# Cortex.net
KiCad netlist of a schematic drawn in Altium Designer
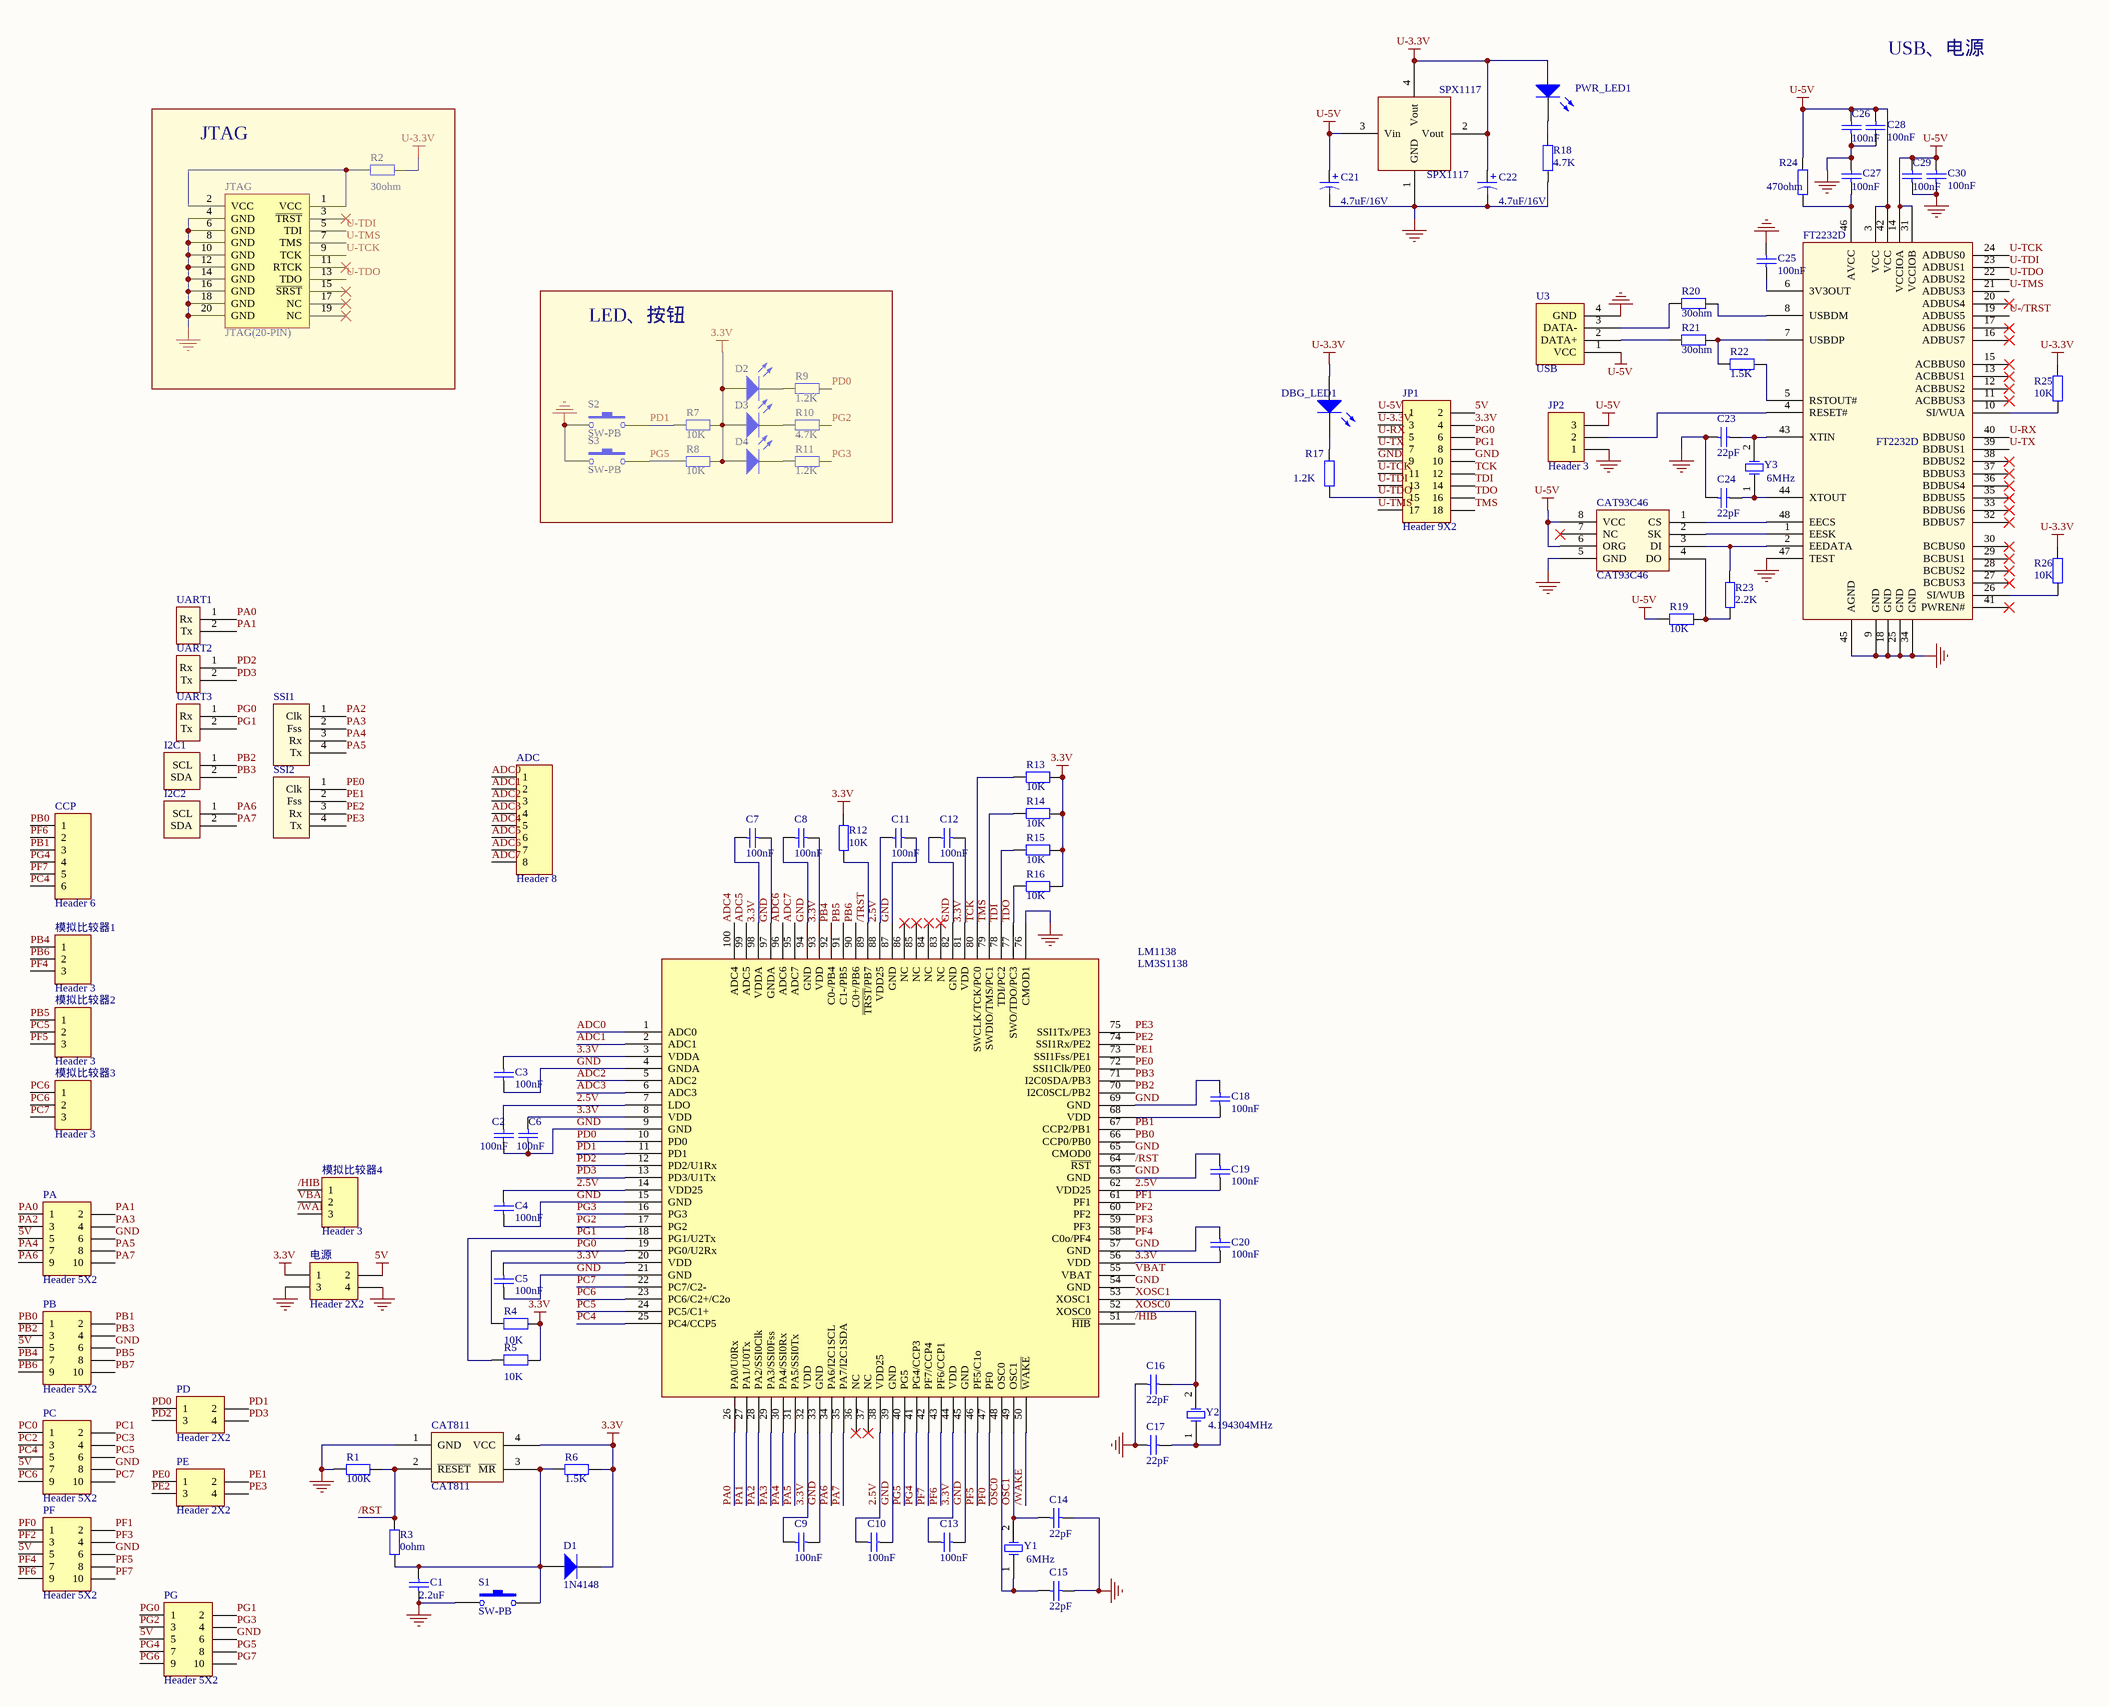
[diagram p0: Cortex.SchDoc]

(export (version "E")
  (design (tool "Eeschema 10.0.6"))
  (components
    (comp (ref "ADC")
      (value "Header 8")
      (footprint "HDR1X8")
      (description "Header, 8-Pin")
      (fields (field (name "PUBLISHER") "Altium Limited"))
      (libsource (lib "自定义库") (part "Header 8"))
    )
    (comp (ref "C1")
      (value "2.2uF")
      (footprint "C0805")
      (description "Capacitor")
      (fields (field (name "Comment") "Cap") (field (name "PUBLISHER") "Altium Limited"))
      (libsource (lib "Miscellaneous Devices") (part "Cap"))
    )
    (comp (ref "C2")
      (value "100nF")
      (footprint "C0805")
      (description "Capacitor")
      (fields (field (name "Comment") "Cap") (field (name "PUBLISHER") "Altium Limited"))
      (libsource (lib "Miscellaneous Devices") (part "Cap"))
    )
    (comp (ref "C3")
      (value "100nF")
      (footprint "C0805")
      (description "Capacitor")
      (fields (field (name "Comment") "Cap") (field (name "PUBLISHER") "Altium Limited"))
      (libsource (lib "Miscellaneous Devices") (part "Cap"))
    )
    (comp (ref "C4")
      (value "100nF")
      (footprint "C0805")
      (description "Capacitor")
      (fields (field (name "Comment") "Cap") (field (name "PUBLISHER") "Altium Limited"))
      (libsource (lib "Miscellaneous Devices") (part "Cap"))
    )
    (comp (ref "C5")
      (value "100nF")
      (footprint "C0805")
      (description "Capacitor")
      (fields (field (name "Comment") "Cap") (field (name "PUBLISHER") "Altium Limited"))
      (libsource (lib "Miscellaneous Devices") (part "Cap"))
    )
    (comp (ref "C6")
      (value "100nF")
      (footprint "C0805")
      (description "Capacitor")
      (fields (field (name "Comment") "Cap") (field (name "PUBLISHER") "Altium Limited"))
      (libsource (lib "Miscellaneous Devices") (part "Cap"))
    )
    (comp (ref "C7")
      (value "100nF")
      (footprint "C0805")
      (description "Capacitor")
      (fields (field (name "Comment") "Cap") (field (name "PUBLISHER") "Altium Limited"))
      (libsource (lib "Miscellaneous Devices") (part "Cap"))
    )
    (comp (ref "C8")
      (value "100nF")
      (footprint "C0805")
      (description "Capacitor")
      (fields (field (name "Comment") "Cap") (field (name "PUBLISHER") "Altium Limited"))
      (libsource (lib "Miscellaneous Devices") (part "Cap"))
    )
    (comp (ref "C9")
      (value "100nF")
      (footprint "C0805")
      (description "Capacitor")
      (fields (field (name "Comment") "Cap") (field (name "PUBLISHER") "Altium Limited"))
      (libsource (lib "Miscellaneous Devices") (part "Cap"))
    )
    (comp (ref "C10")
      (value "100nF")
      (footprint "C0805")
      (description "Capacitor")
      (fields (field (name "Comment") "Cap") (field (name "PUBLISHER") "Altium Limited"))
      (libsource (lib "Miscellaneous Devices") (part "Cap"))
    )
    (comp (ref "C11")
      (value "100nF")
      (footprint "C0805")
      (description "Capacitor")
      (fields (field (name "Comment") "Cap") (field (name "PUBLISHER") "Altium Limited"))
      (libsource (lib "Miscellaneous Devices") (part "Cap"))
    )
    (comp (ref "C12")
      (value "100nF")
      (footprint "C0805")
      (description "Capacitor")
      (fields (field (name "Comment") "Cap") (field (name "PUBLISHER") "Altium Limited"))
      (libsource (lib "Miscellaneous Devices") (part "Cap"))
    )
    (comp (ref "C13")
      (value "100nF")
      (footprint "C0805")
      (description "Capacitor")
      (fields (field (name "Comment") "Cap") (field (name "PUBLISHER") "Altium Limited"))
      (libsource (lib "Miscellaneous Devices") (part "Cap"))
    )
    (comp (ref "C14")
      (value "22pF")
      (footprint "C0805")
      (description "Capacitor")
      (fields (field (name "Comment") "Cap") (field (name "PUBLISHER") "Altium Limited"))
      (libsource (lib "Miscellaneous Devices") (part "Cap"))
    )
    (comp (ref "C15")
      (value "22pF")
      (footprint "C0805")
      (description "Capacitor")
      (fields (field (name "Comment") "Cap") (field (name "PUBLISHER") "Altium Limited"))
      (libsource (lib "Miscellaneous Devices") (part "Cap"))
    )
    (comp (ref "C16")
      (value "22pF")
      (footprint "C0805")
      (description "Capacitor")
      (fields (field (name "Comment") "Cap") (field (name "PUBLISHER") "Altium Limited"))
      (libsource (lib "Miscellaneous Devices") (part "Cap"))
    )
    (comp (ref "C17")
      (value "22pF")
      (footprint "C0805")
      (description "Capacitor")
      (fields (field (name "Comment") "Cap") (field (name "PUBLISHER") "Altium Limited"))
      (libsource (lib "Miscellaneous Devices") (part "Cap"))
    )
    (comp (ref "C18")
      (value "100nF")
      (footprint "C0805")
      (description "Capacitor")
      (fields (field (name "Comment") "Cap") (field (name "PUBLISHER") "Altium Limited"))
      (libsource (lib "Miscellaneous Devices") (part "Cap"))
    )
    (comp (ref "C19")
      (value "100nF")
      (footprint "C0805")
      (description "Capacitor")
      (fields (field (name "Comment") "Cap") (field (name "PUBLISHER") "Altium Limited"))
      (libsource (lib "Miscellaneous Devices") (part "Cap"))
    )
    (comp (ref "C20")
      (value "100nF")
      (footprint "C0805")
      (description "Capacitor")
      (fields (field (name "Comment") "Cap") (field (name "PUBLISHER") "Altium Limited"))
      (libsource (lib "Miscellaneous Devices") (part "Cap"))
    )
    (comp (ref "C21")
      (value "4.7uF/16V")
      (footprint "C1206")
      (description "Polarized Capacitor (Radial)")
      (fields (field (name "Comment") "Cap Pol1") (field (name "PUBLISHER") "Altium Limited"))
      (libsource (lib "Miscellaneous Devices") (part "Cap Pol1"))
    )
    (comp (ref "C22")
      (value "4.7uF/16V")
      (footprint "C1206")
      (description "Polarized Capacitor (Radial)")
      (fields (field (name "Comment") "Cap Pol1") (field (name "PUBLISHER") "Altium Limited"))
      (libsource (lib "Miscellaneous Devices") (part "Cap Pol1"))
    )
    (comp (ref "C23")
      (value "22pF")
      (footprint "C0805")
      (description "Capacitor")
      (fields (field (name "Comment") "Cap") (field (name "PUBLISHER") "Altium Limited"))
      (libsource (lib "Miscellaneous Devices") (part "Cap"))
    )
    (comp (ref "C24")
      (value "22pF")
      (footprint "C0805")
      (description "Capacitor")
      (fields (field (name "Comment") "Cap") (field (name "PUBLISHER") "Altium Limited"))
      (libsource (lib "Miscellaneous Devices") (part "Cap"))
    )
    (comp (ref "C25")
      (value "100nF")
      (footprint "C0805")
      (description "Capacitor")
      (fields (field (name "Comment") "Cap") (field (name "PUBLISHER") "Altium Limited"))
      (libsource (lib "Miscellaneous Devices") (part "Cap"))
    )
    (comp (ref "C26")
      (value "100nF")
      (footprint "C0805")
      (description "Capacitor")
      (fields (field (name "Comment") "Cap") (field (name "PUBLISHER") "Altium Limited"))
      (libsource (lib "Miscellaneous Devices") (part "Cap"))
    )
    (comp (ref "C27")
      (value "100nF")
      (footprint "C0805")
      (description "Capacitor")
      (fields (field (name "Comment") "Cap") (field (name "PUBLISHER") "Altium Limited"))
      (libsource (lib "Miscellaneous Devices") (part "Cap"))
    )
    (comp (ref "C28")
      (value "100nF")
      (footprint "C0805")
      (description "Capacitor")
      (fields (field (name "Comment") "Cap") (field (name "PUBLISHER") "Altium Limited"))
      (libsource (lib "Miscellaneous Devices") (part "Cap"))
    )
    (comp (ref "C29")
      (value "100nF")
      (footprint "C0805")
      (description "Capacitor")
      (fields (field (name "Comment") "Cap") (field (name "PUBLISHER") "Altium Limited"))
      (libsource (lib "Miscellaneous Devices") (part "Cap"))
    )
    (comp (ref "C30")
      (value "100nF")
      (footprint "C0805")
      (description "Capacitor")
      (fields (field (name "Comment") "Cap") (field (name "PUBLISHER") "Altium Limited"))
      (libsource (lib "Miscellaneous Devices") (part "Cap"))
    )
    (comp (ref "CAT93C46") (value "CAT93C46") (footprint "SO8") (libsource (lib "自定义库") (part "CAT93C46")))
    (comp (ref "CAT811") (value "CAT811") (footprint "SOT-143") (libsource (lib "自定义库") (part "CAT811")))
    (comp (ref "CCP")
      (value "Header 6")
      (footprint "HDR1X6")
      (description "Header, 6-Pin")
      (fields (field (name "PUBLISHER") "Altium Limited"))
      (libsource (lib "自定义库") (part "Header 6"))
    )
    (comp (ref "D1")
      (value "1N4148")
      (footprint "DO-35")
      (description "High Conductance Fast Diode")
      (fields (field (name "PUBLISHER") "Altium Limited"))
      (libsource (lib "自定义库") (part "Diode 1N4148"))
    )
    (comp (ref "D2")
      (value "LED2")
      (footprint "3.2X1.6X1.1")
      (description "Typical RED, GREEN, YELLOW, AMBER GaAs LED")
      (fields (field (name "PUBLISHER") "Altium Limited"))
      (libsource (lib "自定义库") (part "LED2"))
    )
    (comp (ref "D3")
      (value "LED2")
      (footprint "3.2X1.6X1.1")
      (description "Typical RED, GREEN, YELLOW, AMBER GaAs LED")
      (fields (field (name "PUBLISHER") "Altium Limited"))
      (libsource (lib "自定义库") (part "LED2"))
    )
    (comp (ref "D4")
      (value "LED2")
      (footprint "3.2X1.6X1.1")
      (description "Typical RED, GREEN, YELLOW, AMBER GaAs LED")
      (fields (field (name "PUBLISHER") "Altium Limited"))
      (libsource (lib "自定义库") (part "LED2"))
    )
    (comp (ref "DBG_LED1")
      (value "LED0")
      (footprint "LED-0")
      (description "Typical INFRARED GaAs LED")
      (fields (field (name "PUBLISHER") "Altium Limited"))
      (libsource (lib "自定义库") (part "LED0"))
    )
    (comp (ref "FT2232D") (value "FT2232D") (footprint "LQFP-48") (libsource (lib "自定义库") (part "FT2232D")))
    (comp (ref "I2C1") (value "I2C") (footprint "HDR1X2") (libsource (lib "自定义库") (part "I2C")))
    (comp (ref "I2C2") (value "I2C") (footprint "HDR1X2") (libsource (lib "自定义库") (part "I2C")))
    (comp (ref "JP1")
      (value "Header 9X2")
      (footprint "HDR2X9")
      (description "Header, 9-Pin, Dual row")
      (fields (field (name "PUBLISHER") "Altium Limited"))
      (libsource (lib "自定义库") (part "Header 9X2"))
    )
    (comp (ref "JP2")
      (value "Header 3")
      (footprint "HDR1X3")
      (description "Header, 3-Pin")
      (fields (field (name "PUBLISHER") "Altium Limited"))
      (libsource (lib "") (part "Header 3_1"))
    )
    (comp (ref "JTAG")
      (value "JTAG(20-PIN)")
      (footprint "IDC-20(2.54)IDE")
      (libsource (lib "自定义库") (part "JTAG(20-PIN)"))
    )
    (comp (ref "LM1138") (value "LM3S1138") (footprint "LQFP-100") (libsource (lib "自定义库") (part "LM3S1138")))
    (comp (ref "PA")
      (value "Header 5X2")
      (footprint "HDR2X5")
      (description "Header, 5-Pin, Dual row")
      (fields (field (name "PUBLISHER") "Altium Limited"))
      (libsource (lib "自定义库") (part "Header 5X2"))
    )
    (comp (ref "PB")
      (value "Header 5X2")
      (footprint "HDR2X5")
      (description "Header, 5-Pin, Dual row")
      (fields (field (name "PUBLISHER") "Altium Limited"))
      (libsource (lib "自定义库") (part "Header 5X2"))
    )
    (comp (ref "PC")
      (value "Header 5X2")
      (footprint "HDR2X5")
      (description "Header, 5-Pin, Dual row")
      (fields (field (name "PUBLISHER") "Altium Limited"))
      (libsource (lib "自定义库") (part "Header 5X2"))
    )
    (comp (ref "PD")
      (value "Header 2X2")
      (footprint "HDR2X2")
      (description "Header, 2-Pin, Dual row")
      (fields (field (name "PUBLISHER") "Altium Limited"))
      (libsource (lib "自定义库") (part "Header 2X2"))
    )
    (comp (ref "PE")
      (value "Header 2X2")
      (footprint "HDR2X2")
      (description "Header, 2-Pin, Dual row")
      (fields (field (name "PUBLISHER") "Altium Limited"))
      (libsource (lib "自定义库") (part "Header 2X2"))
    )
    (comp (ref "PF")
      (value "Header 5X2")
      (footprint "HDR2X5")
      (description "Header, 5-Pin, Dual row")
      (fields (field (name "PUBLISHER") "Altium Limited"))
      (libsource (lib "自定义库") (part "Header 5X2"))
    )
    (comp (ref "PG")
      (value "Header 5X2")
      (footprint "HDR2X5")
      (description "Header, 5-Pin, Dual row")
      (fields (field (name "PUBLISHER") "Altium Limited"))
      (libsource (lib "自定义库") (part "Header 5X2"))
    )
    (comp (ref "PWR_LED1")
      (value "LED0")
      (footprint "LED-0")
      (description "Typical INFRARED GaAs LED")
      (fields (field (name "PUBLISHER") "Altium Limited"))
      (libsource (lib "自定义库") (part "LED0"))
    )
    (comp (ref "R1")
      (value "100K")
      (footprint "C0805")
      (description "Resistor")
      (fields (field (name "Comment") "Res2") (field (name "PUBLISHER") "Altium Limited"))
      (libsource (lib "") (part "Res2_1"))
    )
    (comp (ref "R2")
      (value "30ohm")
      (footprint "C0805")
      (description "Resistor")
      (fields (field (name "Comment") "Res2") (field (name "PUBLISHER") "Altium Limited"))
      (libsource (lib "") (part "Res2_2"))
    )
    (comp (ref "R3")
      (value "0ohm")
      (footprint "C0805")
      (description "Resistor")
      (fields (field (name "Comment") "Res2") (field (name "PUBLISHER") "Altium Limited"))
      (libsource (lib "Miscellaneous Devices") (part "Res2"))
    )
    (comp (ref "R4")
      (value "10K")
      (footprint "C0805")
      (description "Resistor")
      (fields (field (name "Comment") "Res2") (field (name "PUBLISHER") "Altium Limited"))
      (libsource (lib "") (part "Res2_2"))
    )
    (comp (ref "R5")
      (value "10K")
      (footprint "C0805")
      (description "Resistor")
      (fields (field (name "Comment") "Res2") (field (name "PUBLISHER") "Altium Limited"))
      (libsource (lib "") (part "Res2_2"))
    )
    (comp (ref "R6")
      (value "1.5K")
      (footprint "C0805")
      (description "Resistor")
      (fields (field (name "Comment") "Res2") (field (name "PUBLISHER") "Altium Limited"))
      (libsource (lib "") (part "Res2_2"))
    )
    (comp (ref "R7")
      (value "10K")
      (footprint "C0805")
      (description "Resistor")
      (fields (field (name "Comment") "Res2") (field (name "PUBLISHER") "Altium Limited"))
      (libsource (lib "") (part "Res2_2"))
    )
    (comp (ref "R8")
      (value "10K")
      (footprint "C0805")
      (description "Resistor")
      (fields (field (name "Comment") "Res2") (field (name "PUBLISHER") "Altium Limited"))
      (libsource (lib "") (part "Res2_2"))
    )
    (comp (ref "R9")
      (value "1.2K")
      (footprint "C0805")
      (description "Resistor")
      (fields (field (name "Comment") "Res2") (field (name "PUBLISHER") "Altium Limited"))
      (libsource (lib "") (part "Res2_2"))
    )
    (comp (ref "R10")
      (value "4.7K")
      (footprint "C0805")
      (description "Resistor")
      (fields (field (name "Comment") "Res2") (field (name "PUBLISHER") "Altium Limited"))
      (libsource (lib "") (part "Res2_2"))
    )
    (comp (ref "R11")
      (value "1.2K")
      (footprint "C0805")
      (description "Resistor")
      (fields (field (name "Comment") "Res2") (field (name "PUBLISHER") "Altium Limited"))
      (libsource (lib "") (part "Res2_2"))
    )
    (comp (ref "R12")
      (value "10K")
      (footprint "C0805")
      (description "Resistor")
      (fields (field (name "Comment") "Res2") (field (name "PUBLISHER") "Altium Limited"))
      (libsource (lib "") (part "Res2_3"))
    )
    (comp (ref "R13")
      (value "10K")
      (footprint "C0805")
      (description "Resistor")
      (fields (field (name "Comment") "Res2") (field (name "PUBLISHER") "Altium Limited"))
      (libsource (lib "") (part "Res2_1"))
    )
    (comp (ref "R14")
      (value "10K")
      (footprint "C0805")
      (description "Resistor")
      (fields (field (name "Comment") "Res2") (field (name "PUBLISHER") "Altium Limited"))
      (libsource (lib "") (part "Res2_1"))
    )
    (comp (ref "R15")
      (value "10K")
      (footprint "C0805")
      (description "Resistor")
      (fields (field (name "Comment") "Res2") (field (name "PUBLISHER") "Altium Limited"))
      (libsource (lib "") (part "Res2_1"))
    )
    (comp (ref "R16")
      (value "10K")
      (footprint "C0805")
      (description "Resistor")
      (fields (field (name "Comment") "Res2") (field (name "PUBLISHER") "Altium Limited"))
      (libsource (lib "") (part "Res2_1"))
    )
    (comp (ref "R17")
      (value "1.2K")
      (footprint "C0805")
      (description "Resistor")
      (fields (field (name "Comment") "Res2") (field (name "PUBLISHER") "Altium Limited"))
      (libsource (lib "") (part "Res2_3"))
    )
    (comp (ref "R18")
      (value "4.7K")
      (footprint "C0805")
      (description "Resistor")
      (fields (field (name "Comment") "Res2") (field (name "PUBLISHER") "Altium Limited"))
      (libsource (lib "Miscellaneous Devices") (part "Res2"))
    )
    (comp (ref "R19")
      (value "10K")
      (footprint "C0805")
      (description "Resistor")
      (fields (field (name "Comment") "Res2") (field (name "PUBLISHER") "Altium Limited"))
      (libsource (lib "") (part "Res2_1"))
    )
    (comp (ref "R20")
      (value "30ohm")
      (footprint "C0805")
      (description "Resistor")
      (fields (field (name "Comment") "Res2") (field (name "PUBLISHER") "Altium Limited"))
      (libsource (lib "") (part "Res2_1"))
    )
    (comp (ref "R21")
      (value "30ohm")
      (footprint "C0805")
      (description "Resistor")
      (fields (field (name "Comment") "Res2") (field (name "PUBLISHER") "Altium Limited"))
      (libsource (lib "") (part "Res2_1"))
    )
    (comp (ref "R22")
      (value "1.5K")
      (footprint "C0805")
      (description "Resistor")
      (fields (field (name "Comment") "Res2") (field (name "PUBLISHER") "Altium Limited"))
      (libsource (lib "") (part "Res2_1"))
    )
    (comp (ref "R23")
      (value "2.2K")
      (footprint "C0805")
      (description "Resistor")
      (fields (field (name "Comment") "Res2") (field (name "PUBLISHER") "Altium Limited"))
      (libsource (lib "Miscellaneous Devices") (part "Res2"))
    )
    (comp (ref "R24")
      (value "470ohm")
      (footprint "C0805")
      (description "Resistor")
      (fields (field (name "Comment") "Res2") (field (name "PUBLISHER") "Altium Limited"))
      (libsource (lib "") (part "Res2_3"))
    )
    (comp (ref "R25")
      (value "10K")
      (footprint "C0805")
      (description "Resistor")
      (fields (field (name "Comment") "Res2") (field (name "PUBLISHER") "Altium Limited"))
      (libsource (lib "") (part "Res2_3"))
    )
    (comp (ref "R26")
      (value "10K")
      (footprint "C0805")
      (description "Resistor")
      (fields (field (name "Comment") "Res2") (field (name "PUBLISHER") "Altium Limited"))
      (libsource (lib "") (part "Res2_3"))
    )
    (comp (ref "S1")
      (value "SW-PB")
      (footprint "SPST-2")
      (description "Switch")
      (fields (field (name "PUBLISHER") "Altium Limited"))
      (libsource (lib "自定义库") (part "SW-PB"))
    )
    (comp (ref "S2")
      (value "SW-PB")
      (footprint "SPST-2")
      (description "Switch")
      (fields (field (name "PUBLISHER") "Altium Limited"))
      (libsource (lib "自定义库") (part "SW-PB"))
    )
    (comp (ref "S3")
      (value "SW-PB")
      (footprint "SPST-2")
      (description "Switch")
      (fields (field (name "PUBLISHER") "Altium Limited"))
      (libsource (lib "自定义库") (part "SW-PB"))
    )
    (comp (ref "SPX1117") (value "SPX1117") (footprint "SOT223") (libsource (lib "自定义库") (part "SPX1117")))
    (comp (ref "SSI1") (value "SSI") (footprint "HDR1X4") (libsource (lib "自定义库") (part "SSI")))
    (comp (ref "SSI2") (value "SSI") (footprint "HDR1X4") (libsource (lib "自定义库") (part "SSI")))
    (comp (ref "U3") (value "USB") (footprint "USB-B") (libsource (lib "自定义库") (part "USB")))
    (comp (ref "UART1") (value "UART") (footprint "HDR1X2") (libsource (lib "自定义库") (part "UART")))
    (comp (ref "UART2") (value "UART") (footprint "HDR1X2") (libsource (lib "自定义库") (part "UART")))
    (comp (ref "UART3") (value "UART") (footprint "HDR1X2") (libsource (lib "自定义库") (part "UART")))
    (comp (ref "Y1")
      (value "6MHz")
      (footprint "R38")
      (description "Crystal Oscillator")
      (fields (field (name "PUBLISHER") "Altium Limited"))
      (libsource (lib "自定义库") (part "XTAL"))
    )
    (comp (ref "Y2")
      (value "4.194304MHz")
      (footprint "R38")
      (description "Crystal Oscillator")
      (fields (field (name "PUBLISHER") "Altium Limited"))
      (libsource (lib "自定义库") (part "XTAL"))
    )
    (comp (ref "Y3")
      (value "6MHz")
      (footprint "R38")
      (description "Crystal Oscillator")
      (fields (field (name "PUBLISHER") "Altium Limited"))
      (libsource (lib "自定义库") (part "XTAL"))
    )
    (comp (ref "模拟比较器1")
      (value "Header 3")
      (footprint "HDR1X3")
      (description "Header, 3-Pin")
      (fields (field (name "PUBLISHER") "Altium Limited"))
      (libsource (lib "自定义库") (part "Header 3"))
    )
    (comp (ref "模拟比较器2")
      (value "Header 3")
      (footprint "HDR1X3")
      (description "Header, 3-Pin")
      (fields (field (name "PUBLISHER") "Altium Limited"))
      (libsource (lib "自定义库") (part "Header 3"))
    )
    (comp (ref "模拟比较器3")
      (value "Header 3")
      (footprint "HDR1X3")
      (description "Header, 3-Pin")
      (fields (field (name "PUBLISHER") "Altium Limited"))
      (libsource (lib "自定义库") (part "Header 3"))
    )
    (comp (ref "模拟比较器4")
      (value "Header 3")
      (footprint "HDR1X3")
      (description "Header, 3-Pin")
      (fields (field (name "PUBLISHER") "Altium Limited"))
      (libsource (lib "自定义库") (part "Header 3"))
    )
    (comp (ref "电源")
      (value "Header 2X2")
      (footprint "HDR2X2")
      (description "Header, 2-Pin, Dual row")
      (fields (field (name "PUBLISHER") "Altium Limited"))
      (libsource (lib "自定义库") (part "Header 2X2"))
    )
  )
  (nets
    (net (code "1") (name "/2.5V") (class "Default")
      (node (ref "C10") (pin "1") (pinfunction "1_1") (pintype "passive"))
      (node (ref "C11") (pin "2") (pinfunction "2_2") (pintype "passive"))
      (node (ref "C19") (pin "2") (pinfunction "2_2") (pintype "passive"))
      (node (ref "C2") (pin "2") (pinfunction "2_2") (pintype "passive"))
      (node (ref "C4") (pin "2") (pinfunction "2_2") (pintype "passive"))
      (node (ref "LM1138") (pin "14") (pinfunction "VDD25_14") (pintype "passive"))
      (node (ref "LM1138") (pin "38") (pinfunction "VDD25_38") (pintype "passive"))
      (node (ref "LM1138") (pin "62") (pinfunction "VDD25_62") (pintype "passive"))
      (node (ref "LM1138") (pin "7") (pinfunction "LDO_7") (pintype "passive"))
      (node (ref "LM1138") (pin "88") (pinfunction "VDD25_88") (pintype "passive"))
    )
    (net (code "2") (name "/ADC0") (class "Default")
      (node (ref "ADC") (pin "1") (pinfunction "1_1") (pintype "passive"))
      (node (ref "LM1138") (pin "1") (pinfunction "ADC0_1") (pintype "passive"))
    )
    (net (code "3") (name "/ADC1") (class "Default")
      (node (ref "ADC") (pin "2") (pinfunction "2_2") (pintype "passive"))
      (node (ref "LM1138") (pin "2") (pinfunction "ADC1_2") (pintype "passive"))
    )
    (net (code "4") (name "/ADC2") (class "Default")
      (node (ref "ADC") (pin "3") (pinfunction "3_3") (pintype "passive"))
      (node (ref "LM1138") (pin "5") (pinfunction "ADC2_5") (pintype "passive"))
    )
    (net (code "5") (name "/ADC3") (class "Default")
      (node (ref "ADC") (pin "4") (pinfunction "4_4") (pintype "passive"))
      (node (ref "LM1138") (pin "6") (pinfunction "ADC3_6") (pintype "passive"))
    )
    (net (code "6") (name "/ADC4") (class "Default")
      (node (ref "ADC") (pin "5") (pinfunction "5_5") (pintype "passive"))
      (node (ref "LM1138") (pin "100") (pinfunction "ADC4_100") (pintype "passive"))
    )
    (net (code "7") (name "/ADC5") (class "Default")
      (node (ref "ADC") (pin "6") (pinfunction "6_6") (pintype "passive"))
      (node (ref "LM1138") (pin "99") (pinfunction "ADC5_99") (pintype "passive"))
    )
    (net (code "8") (name "/ADC6") (class "Default")
      (node (ref "ADC") (pin "7") (pinfunction "7_7") (pintype "passive"))
      (node (ref "LM1138") (pin "96") (pinfunction "ADC6_96") (pintype "passive"))
    )
    (net (code "9") (name "/ADC7") (class "Default")
      (node (ref "ADC") (pin "8") (pinfunction "8_8") (pintype "passive"))
      (node (ref "LM1138") (pin "95") (pinfunction "ADC7_95") (pintype "passive"))
    )
    (net (code "10") (name "/OSC0") (class "Default")
      (node (ref "C15") (pin "1") (pinfunction "1_1") (pintype "passive"))
      (node (ref "LM1138") (pin "48") (pinfunction "OSC0_48") (pintype "passive"))
      (node (ref "Y1") (pin "1") (pinfunction "OSC1_1") (pintype "passive"))
    )
    (net (code "11") (name "/OSC1") (class "Default")
      (node (ref "C14") (pin "1") (pinfunction "1_1") (pintype "passive"))
      (node (ref "LM1138") (pin "49") (pinfunction "OSC1_49") (pintype "passive"))
      (node (ref "Y1") (pin "2") (pinfunction "OSC2_2") (pintype "passive"))
    )
    (net (code "12") (name "/PA0") (class "Default")
      (node (ref "LM1138") (pin "26") (pinfunction "PA0/U0Rx_26") (pintype "passive"))
      (node (ref "PA") (pin "1") (pinfunction "1_1") (pintype "passive"))
      (node (ref "UART1") (pin "1") (pinfunction "Rx_1") (pintype "passive"))
    )
    (net (code "13") (name "/PA1") (class "Default")
      (node (ref "LM1138") (pin "27") (pinfunction "PA1/U0Tx_27") (pintype "passive"))
      (node (ref "PA") (pin "2") (pinfunction "2_2") (pintype "passive"))
      (node (ref "UART1") (pin "2") (pinfunction "Tx_2") (pintype "passive"))
    )
    (net (code "14") (name "/PA2") (class "Default")
      (node (ref "LM1138") (pin "28") (pinfunction "PA2/SSI0Clk_28") (pintype "passive"))
      (node (ref "PA") (pin "3") (pinfunction "3_3") (pintype "passive"))
      (node (ref "SSI1") (pin "1") (pinfunction "Clk_1") (pintype "passive"))
    )
    (net (code "15") (name "/PA3") (class "Default")
      (node (ref "LM1138") (pin "29") (pinfunction "PA3/SSI0Fss_29") (pintype "passive"))
      (node (ref "PA") (pin "4") (pinfunction "4_4") (pintype "passive"))
      (node (ref "SSI1") (pin "2") (pinfunction "Fss_2") (pintype "passive"))
    )
    (net (code "16") (name "/PA4") (class "Default")
      (node (ref "LM1138") (pin "30") (pinfunction "PA4/SSI0Rx_30") (pintype "passive"))
      (node (ref "PA") (pin "7") (pinfunction "7_7") (pintype "passive"))
      (node (ref "SSI1") (pin "3") (pinfunction "Rx_3") (pintype "passive"))
    )
    (net (code "17") (name "/PA5") (class "Default")
      (node (ref "LM1138") (pin "31") (pinfunction "PA5/SSI0Tx_31") (pintype "passive"))
      (node (ref "PA") (pin "8") (pinfunction "8_8") (pintype "passive"))
      (node (ref "SSI1") (pin "4") (pinfunction "Tx_4") (pintype "passive"))
    )
    (net (code "18") (name "/PA6") (class "Default")
      (node (ref "I2C2") (pin "1") (pinfunction "SCL_1") (pintype "passive"))
      (node (ref "LM1138") (pin "34") (pinfunction "PA6/I2C1SCL_34") (pintype "passive"))
      (node (ref "PA") (pin "9") (pinfunction "9_9") (pintype "passive"))
    )
    (net (code "19") (name "/PA7") (class "Default")
      (node (ref "I2C2") (pin "2") (pinfunction "SDA_2") (pintype "passive"))
      (node (ref "LM1138") (pin "35") (pinfunction "PA7/I2C1SDA_35") (pintype "passive"))
      (node (ref "PA") (pin "10") (pinfunction "10_10") (pintype "passive"))
    )
    (net (code "20") (name "/PB0") (class "Default")
      (node (ref "CCP") (pin "1") (pinfunction "1_1") (pintype "passive"))
      (node (ref "LM1138") (pin "66") (pinfunction "CCP0/PB0_66") (pintype "passive"))
      (node (ref "PB") (pin "1") (pinfunction "1_1") (pintype "passive"))
    )
    (net (code "21") (name "/PB1") (class "Default")
      (node (ref "CCP") (pin "3") (pinfunction "3_3") (pintype "passive"))
      (node (ref "LM1138") (pin "67") (pinfunction "CCP2/PB1_67") (pintype "passive"))
      (node (ref "PB") (pin "2") (pinfunction "2_2") (pintype "passive"))
    )
    (net (code "22") (name "/PB2") (class "Default")
      (node (ref "I2C1") (pin "1") (pinfunction "SCL_1") (pintype "passive"))
      (node (ref "LM1138") (pin "70") (pinfunction "I2C0SCL/PB2_70") (pintype "passive"))
      (node (ref "PB") (pin "3") (pinfunction "3_3") (pintype "passive"))
    )
    (net (code "23") (name "/PB3") (class "Default")
      (node (ref "I2C1") (pin "2") (pinfunction "SDA_2") (pintype "passive"))
      (node (ref "LM1138") (pin "71") (pinfunction "I2C0SDA/PB3_71") (pintype "passive"))
      (node (ref "PB") (pin "4") (pinfunction "4_4") (pintype "passive"))
    )
    (net (code "24") (name "/PB4") (class "Default")
      (node (ref "LM1138") (pin "92") (pinfunction "C0-/PB4_92") (pintype "passive"))
      (node (ref "PB") (pin "7") (pinfunction "7_7") (pintype "passive"))
      (node (ref "模拟比较器1") (pin "1") (pinfunction "1_1") (pintype "passive"))
    )
    (net (code "25") (name "/PB5") (class "Default")
      (node (ref "LM1138") (pin "91") (pinfunction "C1-/PB5_91") (pintype "passive"))
      (node (ref "PB") (pin "8") (pinfunction "8_8") (pintype "passive"))
      (node (ref "模拟比较器2") (pin "1") (pinfunction "1_1") (pintype "passive"))
    )
    (net (code "26") (name "/PB6") (class "Default")
      (node (ref "LM1138") (pin "90") (pinfunction "C0+/PB6_90") (pintype "passive"))
      (node (ref "PB") (pin "9") (pinfunction "9_9") (pintype "passive"))
      (node (ref "模拟比较器1") (pin "2") (pinfunction "2_2") (pintype "passive"))
    )
    (net (code "27") (name "/PB7") (class "Default")
      (node (ref "PB") (pin "10") (pinfunction "10_10") (pintype "passive"))
    )
    (net (code "28") (name "/PC0") (class "Default")
      (node (ref "PC") (pin "1") (pinfunction "1_1") (pintype "passive"))
    )
    (net (code "29") (name "/PC1") (class "Default")
      (node (ref "PC") (pin "2") (pinfunction "2_2") (pintype "passive"))
    )
    (net (code "30") (name "/PC2") (class "Default")
      (node (ref "PC") (pin "3") (pinfunction "3_3") (pintype "passive"))
    )
    (net (code "31") (name "/PC3") (class "Default")
      (node (ref "PC") (pin "4") (pinfunction "4_4") (pintype "passive"))
    )
    (net (code "32") (name "/PC4") (class "Default")
      (node (ref "CCP") (pin "6") (pinfunction "6_6") (pintype "passive"))
      (node (ref "LM1138") (pin "25") (pinfunction "PC4/CCP5_25") (pintype "passive"))
      (node (ref "PC") (pin "5") (pinfunction "5_5") (pintype "passive"))
    )
    (net (code "33") (name "/PC5") (class "Default")
      (node (ref "LM1138") (pin "24") (pinfunction "PC5/C1+_24") (pintype "passive"))
      (node (ref "PC") (pin "6") (pinfunction "6_6") (pintype "passive"))
      (node (ref "模拟比较器2") (pin "2") (pinfunction "2_2") (pintype "passive"))
    )
    (net (code "34") (name "/PC6") (class "Default")
      (node (ref "LM1138") (pin "23") (pinfunction "PC6/C2+/C2o_23") (pintype "passive"))
      (node (ref "PC") (pin "9") (pinfunction "9_9") (pintype "passive"))
      (node (ref "模拟比较器3") (pin "1") (pinfunction "1_1") (pintype "passive"))
      (node (ref "模拟比较器3") (pin "2") (pinfunction "2_2") (pintype "passive"))
    )
    (net (code "35") (name "/PC7") (class "Default")
      (node (ref "LM1138") (pin "22") (pinfunction "PC7/C2-_22") (pintype "passive"))
      (node (ref "PC") (pin "10") (pinfunction "10_10") (pintype "passive"))
      (node (ref "模拟比较器3") (pin "3") (pinfunction "3_3") (pintype "passive"))
    )
    (net (code "36") (name "/PD0") (class "Default")
      (node (ref "LM1138") (pin "10") (pinfunction "PD0_10") (pintype "passive"))
      (node (ref "PD") (pin "1") (pinfunction "1_1") (pintype "passive"))
      (node (ref "R9") (pin "2") (pinfunction "2_2") (pintype "passive"))
    )
    (net (code "37") (name "/PD1") (class "Default")
      (node (ref "LM1138") (pin "11") (pinfunction "PD1_11") (pintype "passive"))
      (node (ref "PD") (pin "2") (pinfunction "2_2") (pintype "passive"))
      (node (ref "R7") (pin "1") (pinfunction "1_1") (pintype "passive"))
      (node (ref "S2") (pin "2") (pinfunction "2_2") (pintype "passive"))
    )
    (net (code "38") (name "/PD2") (class "Default")
      (node (ref "LM1138") (pin "12") (pinfunction "PD2/U1Rx_12") (pintype "passive"))
      (node (ref "PD") (pin "3") (pinfunction "3_3") (pintype "passive"))
      (node (ref "UART2") (pin "1") (pinfunction "Rx_1") (pintype "passive"))
    )
    (net (code "39") (name "/PD3") (class "Default")
      (node (ref "LM1138") (pin "13") (pinfunction "PD3/U1Tx_13") (pintype "passive"))
      (node (ref "PD") (pin "4") (pinfunction "4_4") (pintype "passive"))
      (node (ref "UART2") (pin "2") (pinfunction "Tx_2") (pintype "passive"))
    )
    (net (code "40") (name "/PE0") (class "Default")
      (node (ref "LM1138") (pin "72") (pinfunction "SSI1Clk/PE0_72") (pintype "passive"))
      (node (ref "PE") (pin "1") (pinfunction "1_1") (pintype "passive"))
      (node (ref "SSI2") (pin "1") (pinfunction "Clk_1") (pintype "passive"))
    )
    (net (code "41") (name "/PE1") (class "Default")
      (node (ref "LM1138") (pin "73") (pinfunction "SSI1Fss/PE1_73") (pintype "passive"))
      (node (ref "PE") (pin "2") (pinfunction "2_2") (pintype "passive"))
      (node (ref "SSI2") (pin "2") (pinfunction "Fss_2") (pintype "passive"))
    )
    (net (code "42") (name "/PE2") (class "Default")
      (node (ref "LM1138") (pin "74") (pinfunction "SSI1Rx/PE2_74") (pintype "passive"))
      (node (ref "PE") (pin "3") (pinfunction "3_3") (pintype "passive"))
      (node (ref "SSI2") (pin "3") (pinfunction "Rx_3") (pintype "passive"))
    )
    (net (code "43") (name "/PE3") (class "Default")
      (node (ref "LM1138") (pin "75") (pinfunction "SSI1Tx/PE3_75") (pintype "passive"))
      (node (ref "PE") (pin "4") (pinfunction "4_4") (pintype "passive"))
      (node (ref "SSI2") (pin "4") (pinfunction "Tx_4") (pintype "passive"))
    )
    (net (code "44") (name "/PF0") (class "Default")
      (node (ref "LM1138") (pin "47") (pinfunction "PF0_47") (pintype "passive"))
      (node (ref "PF") (pin "1") (pinfunction "1_1") (pintype "passive"))
    )
    (net (code "45") (name "/PF1") (class "Default")
      (node (ref "LM1138") (pin "61") (pinfunction "PF1_61") (pintype "passive"))
      (node (ref "PF") (pin "2") (pinfunction "2_2") (pintype "passive"))
    )
    (net (code "46") (name "/PF2") (class "Default")
      (node (ref "LM1138") (pin "60") (pinfunction "PF2_60") (pintype "passive"))
      (node (ref "PF") (pin "3") (pinfunction "3_3") (pintype "passive"))
    )
    (net (code "47") (name "/PF3") (class "Default")
      (node (ref "LM1138") (pin "59") (pinfunction "PF3_59") (pintype "passive"))
      (node (ref "PF") (pin "4") (pinfunction "4_4") (pintype "passive"))
    )
    (net (code "48") (name "/PF4") (class "Default")
      (node (ref "LM1138") (pin "58") (pinfunction "C0o/PF4_58") (pintype "passive"))
      (node (ref "PF") (pin "7") (pinfunction "7_7") (pintype "passive"))
      (node (ref "模拟比较器1") (pin "3") (pinfunction "3_3") (pintype "passive"))
    )
    (net (code "49") (name "/PF5") (class "Default")
      (node (ref "LM1138") (pin "46") (pinfunction "PF5/C1o_46") (pintype "passive"))
      (node (ref "PF") (pin "8") (pinfunction "8_8") (pintype "passive"))
      (node (ref "模拟比较器2") (pin "3") (pinfunction "3_3") (pintype "passive"))
    )
    (net (code "50") (name "/PF6") (class "Default")
      (node (ref "CCP") (pin "2") (pinfunction "2_2") (pintype "passive"))
      (node (ref "LM1138") (pin "43") (pinfunction "PF6/CCP1_43") (pintype "passive"))
      (node (ref "PF") (pin "9") (pinfunction "9_9") (pintype "passive"))
    )
    (net (code "51") (name "/PF7") (class "Default")
      (node (ref "CCP") (pin "5") (pinfunction "5_5") (pintype "passive"))
      (node (ref "LM1138") (pin "42") (pinfunction "PF7/CCP4_42") (pintype "passive"))
      (node (ref "PF") (pin "10") (pinfunction "10_10") (pintype "passive"))
    )
    (net (code "52") (name "/PG0") (class "Default")
      (node (ref "JP1") (pin "6") (pinfunction "6_6") (pintype "passive"))
      (node (ref "LM1138") (pin "19") (pinfunction "PG0/U2Rx_19") (pintype "passive"))
      (node (ref "PG") (pin "1") (pinfunction "1_1") (pintype "passive"))
      (node (ref "R4") (pin "1") (pinfunction "1_1") (pintype "passive"))
      (node (ref "UART3") (pin "1") (pinfunction "Rx_1") (pintype "passive"))
    )
    (net (code "53") (name "/PG1") (class "Default")
      (node (ref "JP1") (pin "8") (pinfunction "8_8") (pintype "passive"))
      (node (ref "LM1138") (pin "18") (pinfunction "PG1/U2Tx_18") (pintype "passive"))
      (node (ref "PG") (pin "2") (pinfunction "2_2") (pintype "passive"))
      (node (ref "R5") (pin "1") (pinfunction "1_1") (pintype "passive"))
      (node (ref "UART3") (pin "2") (pinfunction "Tx_2") (pintype "passive"))
    )
    (net (code "54") (name "/PG2") (class "Default")
      (node (ref "LM1138") (pin "17") (pinfunction "PG2_17") (pintype "passive"))
      (node (ref "PG") (pin "3") (pinfunction "3_3") (pintype "passive"))
      (node (ref "R10") (pin "2") (pinfunction "2_2") (pintype "passive"))
    )
    (net (code "55") (name "/PG3") (class "Default")
      (node (ref "LM1138") (pin "16") (pinfunction "PG3_16") (pintype "passive"))
      (node (ref "PG") (pin "4") (pinfunction "4_4") (pintype "passive"))
      (node (ref "R11") (pin "2") (pinfunction "2_2") (pintype "passive"))
    )
    (net (code "56") (name "/PG4") (class "Default")
      (node (ref "CCP") (pin "4") (pinfunction "4_4") (pintype "passive"))
      (node (ref "LM1138") (pin "41") (pinfunction "PG4/CCP3_41") (pintype "passive"))
      (node (ref "PG") (pin "7") (pinfunction "7_7") (pintype "passive"))
    )
    (net (code "57") (name "/PG5") (class "Default")
      (node (ref "LM1138") (pin "40") (pinfunction "PG5_40") (pintype "passive"))
      (node (ref "PG") (pin "8") (pinfunction "8_8") (pintype "passive"))
      (node (ref "R8") (pin "1") (pinfunction "1_1") (pintype "passive"))
      (node (ref "S3") (pin "2") (pinfunction "2_2") (pintype "passive"))
    )
    (net (code "58") (name "/PG6") (class "Default")
      (node (ref "PG") (pin "9") (pinfunction "9_9") (pintype "passive"))
    )
    (net (code "59") (name "/PG7") (class "Default")
      (node (ref "PG") (pin "10") (pinfunction "10_10") (pintype "passive"))
    )
    (net (code "60") (name "/TCK") (class "Default")
      (node (ref "JP1") (pin "12") (pinfunction "12_12") (pintype "passive"))
      (node (ref "LM1138") (pin "80") (pinfunction "SWCLK/TCK/PC0_80") (pintype "passive"))
      (node (ref "R13") (pin "2") (pinfunction "2_2") (pintype "passive"))
    )
    (net (code "61") (name "/TDI") (class "Default")
      (node (ref "JP1") (pin "14") (pinfunction "14_14") (pintype "passive"))
      (node (ref "LM1138") (pin "78") (pinfunction "TDI/PC2_78") (pintype "passive"))
      (node (ref "R15") (pin "2") (pinfunction "2_2") (pintype "passive"))
    )
    (net (code "62") (name "/TDO") (class "Default")
      (node (ref "JP1") (pin "16") (pinfunction "16_16") (pintype "passive"))
      (node (ref "LM1138") (pin "77") (pinfunction "SWO/TDO/PC3_77") (pintype "passive"))
      (node (ref "R16") (pin "2") (pinfunction "2_2") (pintype "passive"))
    )
    (net (code "63") (name "/TMS") (class "Default")
      (node (ref "JP1") (pin "18") (pinfunction "18_18") (pintype "passive"))
      (node (ref "LM1138") (pin "79") (pinfunction "SWDIO/TMS/PC1_79") (pintype "passive"))
      (node (ref "R14") (pin "2") (pinfunction "2_2") (pintype "passive"))
    )
    (net (code "64") (name "/U-RX") (class "Default")
      (node (ref "FT2232D") (pin "40") (pinfunction "BDBUS0_40") (pintype "passive"))
      (node (ref "JP1") (pin "5") (pinfunction "5_5") (pintype "passive"))
    )
    (net (code "65") (name "/U-TCK") (class "Default")
      (node (ref "FT2232D") (pin "24") (pinfunction "ADBUS0_24") (pintype "passive"))
      (node (ref "JP1") (pin "11") (pinfunction "11_11") (pintype "passive"))
      (node (ref "JTAG") (pin "9") (pinfunction "TCK_9") (pintype "passive"))
    )
    (net (code "66") (name "/U-TDI") (class "Default")
      (node (ref "FT2232D") (pin "23") (pinfunction "ADBUS1_23") (pintype "passive"))
      (node (ref "JP1") (pin "13") (pinfunction "13_13") (pintype "passive"))
      (node (ref "JTAG") (pin "5") (pinfunction "TDI_5") (pintype "passive"))
    )
    (net (code "67") (name "/U-TDO") (class "Default")
      (node (ref "FT2232D") (pin "22") (pinfunction "ADBUS2_22") (pintype "passive"))
      (node (ref "JP1") (pin "15") (pinfunction "15_15") (pintype "passive"))
      (node (ref "JTAG") (pin "13") (pinfunction "TDO_13") (pintype "passive"))
      (node (ref "R17") (pin "1") (pinfunction "1_1") (pintype "passive"))
    )
    (net (code "68") (name "/U-TMS") (class "Default")
      (node (ref "FT2232D") (pin "21") (pinfunction "ADBUS3_21") (pintype "passive"))
      (node (ref "JP1") (pin "17") (pinfunction "17_17") (pintype "passive"))
      (node (ref "JTAG") (pin "7") (pinfunction "TMS_7") (pintype "passive"))
    )
    (net (code "69") (name "/U-TX") (class "Default")
      (node (ref "FT2232D") (pin "39") (pinfunction "BDBUS1_39") (pintype "passive"))
      (node (ref "JP1") (pin "7") (pinfunction "7_7") (pintype "passive"))
    )
    (net (code "70") (name "/U-{slash}TRST") (class "Default")
      (node (ref "FT2232D") (pin "19") (pinfunction "ADBUS5_19") (pintype "passive"))
    )
    (net (code "71") (name "/VBAT") (class "Default")
      (node (ref "LM1138") (pin "55") (pinfunction "VBAT_55") (pintype "passive"))
      (node (ref "模拟比较器4") (pin "2") (pinfunction "2_2") (pintype "passive"))
    )
    (net (code "72") (name "/XOSC0") (class "Default")
      (node (ref "C16") (pin "2") (pinfunction "2_2") (pintype "passive"))
      (node (ref "LM1138") (pin "52") (pinfunction "XOSC0_52") (pintype "passive"))
      (node (ref "Y2") (pin "2") (pinfunction "OSC2_2") (pintype "passive"))
    )
    (net (code "73") (name "/XOSC1") (class "Default")
      (node (ref "C17") (pin "2") (pinfunction "2_2") (pintype "passive"))
      (node (ref "LM1138") (pin "53") (pinfunction "XOSC1_53") (pintype "passive"))
      (node (ref "Y2") (pin "1") (pinfunction "OSC1_1") (pintype "passive"))
    )
    (net (code "74") (name "/{slash}HIB") (class "Default")
      (node (ref "LM1138") (pin "51") (pinfunction "~{HIB}_51") (pintype "passive"))
      (node (ref "模拟比较器4") (pin "1") (pinfunction "1_1") (pintype "passive"))
    )
    (net (code "75") (name "/{slash}RST") (class "Default")
      (node (ref "CAT811") (pin "2") (pinfunction "~{RESET}_2") (pintype "passive"))
      (node (ref "LM1138") (pin "64") (pinfunction "~{RST}_64") (pintype "passive"))
      (node (ref "R1") (pin "1") (pinfunction "1_1") (pintype "passive"))
      (node (ref "R3") (pin "1") (pinfunction "1_1") (pintype "passive"))
    )
    (net (code "76") (name "/{slash}TRST") (class "Default")
      (node (ref "LM1138") (pin "89") (pinfunction "~{TRST}/PB7_89") (pintype "passive"))
      (node (ref "R12") (pin "1") (pinfunction "1_1") (pintype "passive"))
    )
    (net (code "77") (name "/{slash}WAKE") (class "Default")
      (node (ref "LM1138") (pin "50") (pinfunction "~{WAKE}_50") (pintype "passive"))
      (node (ref "模拟比较器4") (pin "3") (pinfunction "3_3") (pintype "passive"))
    )
    (net (code "78") (name "3.3V") (class "Default")
      (node (ref "C12") (pin "1") (pinfunction "1_1") (pintype "passive"))
      (node (ref "C13") (pin "1") (pinfunction "1_1") (pintype "passive"))
      (node (ref "C20") (pin "2") (pinfunction "2_2") (pintype "passive"))
      (node (ref "C3") (pin "2") (pinfunction "2_2") (pintype "passive"))
      (node (ref "C5") (pin "2") (pinfunction "2_2") (pintype "passive"))
      (node (ref "C6") (pin "2") (pinfunction "2_2") (pintype "passive"))
      (node (ref "C7") (pin "2") (pinfunction "2_2") (pintype "passive"))
      (node (ref "C8") (pin "1") (pinfunction "1_1") (pintype "passive"))
      (node (ref "C9") (pin "2") (pinfunction "2_2") (pintype "passive"))
      (node (ref "CAT811") (pin "4") (pinfunction "VCC_4") (pintype "passive"))
      (node (ref "D1") (pin "2") (pinfunction "K_2") (pintype "passive"))
      (node (ref "D2") (pin "1") (pinfunction "A_1") (pintype "passive"))
      (node (ref "D3") (pin "1") (pinfunction "A_1") (pintype "passive"))
      (node (ref "D4") (pin "1") (pinfunction "A_1") (pintype "passive"))
      (node (ref "JP1") (pin "4") (pinfunction "4_4") (pintype "passive"))
      (node (ref "LM1138") (pin "20") (pinfunction "VDD_20") (pintype "passive"))
      (node (ref "LM1138") (pin "3") (pinfunction "VDDA_3") (pintype "passive"))
      (node (ref "LM1138") (pin "32") (pinfunction "VDD_32") (pintype "passive"))
      (node (ref "LM1138") (pin "44") (pinfunction "VDD_44") (pintype "passive"))
      (node (ref "LM1138") (pin "56") (pinfunction "VDD_56") (pintype "passive"))
      (node (ref "LM1138") (pin "8") (pinfunction "VDD_8") (pintype "passive"))
      (node (ref "LM1138") (pin "81") (pinfunction "VDD_81") (pintype "passive"))
      (node (ref "LM1138") (pin "93") (pinfunction "VDD_93") (pintype "passive"))
      (node (ref "LM1138") (pin "98") (pinfunction "VDDA_98") (pintype "passive"))
      (node (ref "R12") (pin "2") (pinfunction "2_2") (pintype "passive"))
      (node (ref "R13") (pin "1") (pinfunction "1_1") (pintype "passive"))
      (node (ref "R14") (pin "1") (pinfunction "1_1") (pintype "passive"))
      (node (ref "R15") (pin "1") (pinfunction "1_1") (pintype "passive"))
      (node (ref "R16") (pin "1") (pinfunction "1_1") (pintype "passive"))
      (node (ref "R4") (pin "2") (pinfunction "2_2") (pintype "passive"))
      (node (ref "R5") (pin "2") (pinfunction "2_2") (pintype "passive"))
      (node (ref "R6") (pin "2") (pinfunction "2_2") (pintype "passive"))
      (node (ref "R7") (pin "2") (pinfunction "2_2") (pintype "passive"))
      (node (ref "R8") (pin "2") (pinfunction "2_2") (pintype "passive"))
      (node (ref "电源") (pin "1") (pinfunction "1_1") (pintype "passive"))
    )
    (net (code "79") (name "5V") (class "Default")
      (node (ref "JP1") (pin "2") (pinfunction "2_2") (pintype "passive"))
      (node (ref "PA") (pin "5") (pinfunction "5_5") (pintype "passive"))
      (node (ref "PB") (pin "5") (pinfunction "5_5") (pintype "passive"))
      (node (ref "PC") (pin "7") (pinfunction "7_7") (pintype "passive"))
      (node (ref "PF") (pin "5") (pinfunction "5_5") (pintype "passive"))
      (node (ref "PG") (pin "5") (pinfunction "5_5") (pintype "passive"))
      (node (ref "电源") (pin "2") (pinfunction "2_2") (pintype "passive"))
    )
    (net (code "80") (name "GND") (class "Default")
      (node (ref "C1") (pin "1") (pinfunction "1_1") (pintype "passive"))
      (node (ref "C10") (pin "2") (pinfunction "2_2") (pintype "passive"))
      (node (ref "C11") (pin "1") (pinfunction "1_1") (pintype "passive"))
      (node (ref "C12") (pin "2") (pinfunction "2_2") (pintype "passive"))
      (node (ref "C13") (pin "2") (pinfunction "2_2") (pintype "passive"))
      (node (ref "C14") (pin "2") (pinfunction "2_2") (pintype "passive"))
      (node (ref "C15") (pin "2") (pinfunction "2_2") (pintype "passive"))
      (node (ref "C16") (pin "1") (pinfunction "1_1") (pintype "passive"))
      (node (ref "C17") (pin "1") (pinfunction "1_1") (pintype "passive"))
      (node (ref "C18") (pin "1") (pinfunction "1_1") (pintype "passive"))
      (node (ref "C19") (pin "1") (pinfunction "1_1") (pintype "passive"))
      (node (ref "C2") (pin "1") (pinfunction "1_1") (pintype "passive"))
      (node (ref "C20") (pin "1") (pinfunction "1_1") (pintype "passive"))
      (node (ref "C21") (pin "2") (pinfunction "2_2") (pintype "passive"))
      (node (ref "C22") (pin "2") (pinfunction "2_2") (pintype "passive"))
      (node (ref "C23") (pin "1") (pinfunction "1_1") (pintype "passive"))
      (node (ref "C24") (pin "1") (pinfunction "1_1") (pintype "passive"))
      (node (ref "C25") (pin "2") (pinfunction "2_2") (pintype "passive"))
      (node (ref "C26") (pin "2") (pinfunction "2_2") (pintype "passive"))
      (node (ref "C27") (pin "1") (pinfunction "1_1") (pintype "passive"))
      (node (ref "C28") (pin "2") (pinfunction "2_2") (pintype "passive"))
      (node (ref "C29") (pin "2") (pinfunction "2_2") (pintype "passive"))
      (node (ref "C3") (pin "1") (pinfunction "1_1") (pintype "passive"))
      (node (ref "C30") (pin "2") (pinfunction "2_2") (pintype "passive"))
      (node (ref "C4") (pin "1") (pinfunction "1_1") (pintype "passive"))
      (node (ref "C5") (pin "1") (pinfunction "1_1") (pintype "passive"))
      (node (ref "C6") (pin "1") (pinfunction "1_1") (pintype "passive"))
      (node (ref "C7") (pin "1") (pinfunction "1_1") (pintype "passive"))
      (node (ref "C8") (pin "2") (pinfunction "2_2") (pintype "passive"))
      (node (ref "C9") (pin "1") (pinfunction "1_1") (pintype "passive"))
      (node (ref "CAT811") (pin "1") (pinfunction "GND_1") (pintype "passive"))
      (node (ref "CAT93C46") (pin "5") (pinfunction "GND_5") (pintype "passive"))
      (node (ref "FT2232D") (pin "18") (pinfunction "GND_18") (pintype "passive"))
      (node (ref "FT2232D") (pin "25") (pinfunction "GND_25") (pintype "passive"))
      (node (ref "FT2232D") (pin "34") (pinfunction "GND_34") (pintype "passive"))
      (node (ref "FT2232D") (pin "45") (pinfunction "AGND_45") (pintype "passive"))
      (node (ref "FT2232D") (pin "47") (pinfunction "TEST_47") (pintype "passive"))
      (node (ref "FT2232D") (pin "9") (pinfunction "GND_9") (pintype "passive"))
      (node (ref "JP1") (pin "10") (pinfunction "10_10") (pintype "passive"))
      (node (ref "JP1") (pin "9") (pinfunction "9_9") (pintype "passive"))
      (node (ref "JP2") (pin "1") (pinfunction "1_1") (pintype "passive"))
      (node (ref "JTAG") (pin "10") (pinfunction "GND_10") (pintype "passive"))
      (node (ref "JTAG") (pin "12") (pinfunction "GND_12") (pintype "passive"))
      (node (ref "JTAG") (pin "14") (pinfunction "GND_14") (pintype "passive"))
      (node (ref "JTAG") (pin "16") (pinfunction "GND_16") (pintype "passive"))
      (node (ref "JTAG") (pin "18") (pinfunction "GND_18") (pintype "passive"))
      (node (ref "JTAG") (pin "20") (pinfunction "GND_20") (pintype "passive"))
      (node (ref "JTAG") (pin "4") (pinfunction "GND_4") (pintype "passive"))
      (node (ref "JTAG") (pin "6") (pinfunction "GND_6") (pintype "passive"))
      (node (ref "JTAG") (pin "8") (pinfunction "GND_8") (pintype "passive"))
      (node (ref "LM1138") (pin "15") (pinfunction "GND_15") (pintype "passive"))
      (node (ref "LM1138") (pin "21") (pinfunction "GND_21") (pintype "passive"))
      (node (ref "LM1138") (pin "33") (pinfunction "GND_33") (pintype "passive"))
      (node (ref "LM1138") (pin "39") (pinfunction "GND_39") (pintype "passive"))
      (node (ref "LM1138") (pin "4") (pinfunction "GNDA_4") (pintype "passive"))
      (node (ref "LM1138") (pin "45") (pinfunction "GND_45") (pintype "passive"))
      (node (ref "LM1138") (pin "54") (pinfunction "GND_54") (pintype "passive"))
      (node (ref "LM1138") (pin "57") (pinfunction "GND_57") (pintype "passive"))
      (node (ref "LM1138") (pin "63") (pinfunction "GND_63") (pintype "passive"))
      (node (ref "LM1138") (pin "65") (pinfunction "CMOD0_65") (pintype "passive"))
      (node (ref "LM1138") (pin "69") (pinfunction "GND_69") (pintype "passive"))
      (node (ref "LM1138") (pin "76") (pinfunction "CMOD1_76") (pintype "passive"))
      (node (ref "LM1138") (pin "82") (pinfunction "GND_82") (pintype "passive"))
      (node (ref "LM1138") (pin "87") (pinfunction "GND_87") (pintype "passive"))
      (node (ref "LM1138") (pin "9") (pinfunction "GND_9") (pintype "passive"))
      (node (ref "LM1138") (pin "94") (pinfunction "GND_94") (pintype "passive"))
      (node (ref "LM1138") (pin "97") (pinfunction "GNDA_97") (pintype "passive"))
      (node (ref "PA") (pin "6") (pinfunction "6_6") (pintype "passive"))
      (node (ref "PB") (pin "6") (pinfunction "6_6") (pintype "passive"))
      (node (ref "PC") (pin "8") (pinfunction "8_8") (pintype "passive"))
      (node (ref "PF") (pin "6") (pinfunction "6_6") (pintype "passive"))
      (node (ref "PG") (pin "6") (pinfunction "6_6") (pintype "passive"))
      (node (ref "R1") (pin "2") (pinfunction "2_2") (pintype "passive"))
      (node (ref "R18") (pin "2") (pinfunction "2_2") (pintype "passive"))
      (node (ref "S1") (pin "1") (pinfunction "1_1") (pintype "passive"))
      (node (ref "S2") (pin "1") (pinfunction "1_1") (pintype "passive"))
      (node (ref "S3") (pin "1") (pinfunction "1_1") (pintype "passive"))
      (node (ref "SPX1117") (pin "1") (pinfunction "GND_1") (pintype "passive"))
      (node (ref "U3") (pin "4") (pinfunction "GND_4") (pintype "passive"))
      (node (ref "电源") (pin "3") (pinfunction "3_3") (pintype "passive"))
      (node (ref "电源") (pin "4") (pinfunction "4_4") (pintype "passive"))
    )
    (net (code "81") (name "Net-(C18-Pad2)") (class "Default")
      (node (ref "C18") (pin "2") (pinfunction "2_2") (pintype "passive"))
      (node (ref "LM1138") (pin "68") (pinfunction "VDD_68") (pintype "passive"))
    )
    (net (code "82") (name "Net-(CAT93C46-CS)") (class "Default")
      (node (ref "CAT93C46") (pin "1") (pinfunction "CS_1") (pintype "passive"))
      (node (ref "FT2232D") (pin "48") (pinfunction "EECS_48") (pintype "passive"))
    )
    (net (code "83") (name "Net-(CAT93C46-DI)") (class "Default")
      (node (ref "CAT93C46") (pin "3") (pinfunction "DI_3") (pintype "passive"))
      (node (ref "FT2232D") (pin "2") (pinfunction "EEDATA_2") (pintype "passive"))
      (node (ref "R23") (pin "1") (pinfunction "1_1") (pintype "passive"))
    )
    (net (code "84") (name "Net-(CAT93C46-DO)") (class "Default")
      (node (ref "CAT93C46") (pin "4") (pinfunction "DO_4") (pintype "passive"))
      (node (ref "R19") (pin "1") (pinfunction "1_1") (pintype "passive"))
      (node (ref "R23") (pin "2") (pinfunction "2_2") (pintype "passive"))
    )
    (net (code "85") (name "Net-(CAT93C46-SK)") (class "Default")
      (node (ref "CAT93C46") (pin "2") (pinfunction "SK_2") (pintype "passive"))
      (node (ref "FT2232D") (pin "1") (pinfunction "EESK_1") (pintype "passive"))
    )
    (net (code "86") (name "Net-(CAT811-~{MR})") (class "Default")
      (node (ref "C1") (pin "2") (pinfunction "2_2") (pintype "passive"))
      (node (ref "CAT811") (pin "3") (pinfunction "~{MR}_3") (pintype "passive"))
      (node (ref "D1") (pin "1") (pinfunction "A_1") (pintype "passive"))
      (node (ref "R3") (pin "2") (pinfunction "2_2") (pintype "passive"))
      (node (ref "R6") (pin "1") (pinfunction "1_1") (pintype "passive"))
      (node (ref "S1") (pin "2") (pinfunction "2_2") (pintype "passive"))
    )
    (net (code "87") (name "Net-(D2-K)") (class "Default")
      (node (ref "D2") (pin "2") (pinfunction "K_2") (pintype "passive"))
      (node (ref "R9") (pin "1") (pinfunction "1_1") (pintype "passive"))
    )
    (net (code "88") (name "Net-(D3-K)") (class "Default")
      (node (ref "D3") (pin "2") (pinfunction "K_2") (pintype "passive"))
      (node (ref "R10") (pin "1") (pinfunction "1_1") (pintype "passive"))
    )
    (net (code "89") (name "Net-(D4-K)") (class "Default")
      (node (ref "D4") (pin "2") (pinfunction "K_2") (pintype "passive"))
      (node (ref "R11") (pin "1") (pinfunction "1_1") (pintype "passive"))
    )
    (net (code "90") (name "Net-(DBG_LED1-K)") (class "Default")
      (node (ref "DBG_LED1") (pin "2") (pinfunction "K_2") (pintype "passive"))
      (node (ref "R17") (pin "2") (pinfunction "2_2") (pintype "passive"))
    )
    (net (code "91") (name "Net-(FT2232D-3V3OUT)") (class "Default")
      (node (ref "C25") (pin "1") (pinfunction "1_1") (pintype "passive"))
      (node (ref "FT2232D") (pin "6") (pinfunction "3V3OUT_6") (pintype "passive"))
    )
    (net (code "92") (name "Net-(FT2232D-AVCC)") (class "Default")
      (node (ref "C27") (pin "2") (pinfunction "2_2") (pintype "passive"))
      (node (ref "FT2232D") (pin "46") (pinfunction "AVCC_46") (pintype "passive"))
      (node (ref "R24") (pin "1") (pinfunction "1_1") (pintype "passive"))
    )
    (net (code "93") (name "Net-(FT2232D-RESET#)") (class "Default")
      (node (ref "FT2232D") (pin "4") (pinfunction "RESET#_4") (pintype "passive"))
      (node (ref "JP2") (pin "2") (pinfunction "2_2") (pintype "passive"))
    )
    (net (code "94") (name "Net-(FT2232D-RSTOUT#)") (class "Default")
      (node (ref "FT2232D") (pin "5") (pinfunction "RSTOUT#_5") (pintype "passive"))
      (node (ref "R22") (pin "1") (pinfunction "1_1") (pintype "passive"))
    )
    (net (code "95") (name "Net-(FT2232D-SI{slash}WUA)") (class "Default")
      (node (ref "FT2232D") (pin "10") (pinfunction "SI/WUA_10") (pintype "passive"))
      (node (ref "R25") (pin "1") (pinfunction "1_1") (pintype "passive"))
    )
    (net (code "96") (name "Net-(FT2232D-SI{slash}WUB)") (class "Default")
      (node (ref "FT2232D") (pin "26") (pinfunction "SI/WUB_26") (pintype "passive"))
      (node (ref "R26") (pin "1") (pinfunction "1_1") (pintype "passive"))
    )
    (net (code "97") (name "Net-(FT2232D-USBDM)") (class "Default")
      (node (ref "FT2232D") (pin "8") (pinfunction "USBDM_8") (pintype "passive"))
      (node (ref "R20") (pin "1") (pinfunction "1_1") (pintype "passive"))
    )
    (net (code "98") (name "Net-(FT2232D-USBDP)") (class "Default")
      (node (ref "FT2232D") (pin "7") (pinfunction "USBDP_7") (pintype "passive"))
      (node (ref "R21") (pin "1") (pinfunction "1_1") (pintype "passive"))
      (node (ref "R22") (pin "2") (pinfunction "2_2") (pintype "passive"))
    )
    (net (code "99") (name "Net-(FT2232D-XTIN)") (class "Default")
      (node (ref "C23") (pin "2") (pinfunction "2_2") (pintype "passive"))
      (node (ref "FT2232D") (pin "43") (pinfunction "XTIN_43") (pintype "passive"))
      (node (ref "Y3") (pin "2") (pinfunction "OSC2_2") (pintype "passive"))
    )
    (net (code "100") (name "Net-(FT2232D-XTOUT)") (class "Default")
      (node (ref "C24") (pin "2") (pinfunction "2_2") (pintype "passive"))
      (node (ref "FT2232D") (pin "44") (pinfunction "XTOUT_44") (pintype "passive"))
      (node (ref "Y3") (pin "1") (pinfunction "OSC1_1") (pintype "passive"))
    )
    (net (code "101") (name "Net-(JTAG-VCC-Pad1)") (class "Default")
      (node (ref "JTAG") (pin "1") (pinfunction "VCC_1") (pintype "passive"))
      (node (ref "JTAG") (pin "2") (pinfunction "VCC_2") (pintype "passive"))
      (node (ref "R2") (pin "1") (pinfunction "1_1") (pintype "passive"))
    )
    (net (code "102") (name "Net-(PWR_LED1-K)") (class "Default")
      (node (ref "PWR_LED1") (pin "2") (pinfunction "K_2") (pintype "passive"))
      (node (ref "R18") (pin "1") (pinfunction "1_1") (pintype "passive"))
    )
    (net (code "103") (name "Net-(U3-DATA+)") (class "Default")
      (node (ref "R21") (pin "2") (pinfunction "2_2") (pintype "passive"))
      (node (ref "U3") (pin "2") (pinfunction "DATA+_2") (pintype "passive"))
    )
    (net (code "104") (name "Net-(U3-DATA-)") (class "Default")
      (node (ref "R20") (pin "2") (pinfunction "2_2") (pintype "passive"))
      (node (ref "U3") (pin "3") (pinfunction "DATA-_3") (pintype "passive"))
    )
    (net (code "105") (name "U-3.3V") (class "Default")
      (node (ref "C22") (pin "1") (pinfunction "1_1") (pintype "passive"))
      (node (ref "DBG_LED1") (pin "1") (pinfunction "A_1") (pintype "passive"))
      (node (ref "JP1") (pin "3") (pinfunction "3_3") (pintype "passive"))
      (node (ref "PWR_LED1") (pin "1") (pinfunction "A_1") (pintype "passive"))
      (node (ref "R2") (pin "2") (pinfunction "2_2") (pintype "passive"))
      (node (ref "R25") (pin "2") (pinfunction "2_2") (pintype "passive"))
      (node (ref "R26") (pin "2") (pinfunction "2_2") (pintype "passive"))
      (node (ref "SPX1117") (pin "2") (pinfunction "Vout_2") (pintype "passive"))
      (node (ref "SPX1117") (pin "4") (pinfunction "Vout_4") (pintype "passive"))
    )
    (net (code "106") (name "U-5V") (class "Default")
      (node (ref "C21") (pin "1") (pinfunction "1_1") (pintype "passive"))
      (node (ref "C26") (pin "1") (pinfunction "1_1") (pintype "passive"))
      (node (ref "C28") (pin "1") (pinfunction "1_1") (pintype "passive"))
      (node (ref "C29") (pin "1") (pinfunction "1_1") (pintype "passive"))
      (node (ref "C30") (pin "1") (pinfunction "1_1") (pintype "passive"))
      (node (ref "CAT93C46") (pin "6") (pinfunction "ORG_6") (pintype "passive"))
      (node (ref "CAT93C46") (pin "8") (pinfunction "VCC_8") (pintype "passive"))
      (node (ref "FT2232D") (pin "14") (pinfunction "VCCIOA_14") (pintype "passive"))
      (node (ref "FT2232D") (pin "3") (pinfunction "VCC_3") (pintype "passive"))
      (node (ref "FT2232D") (pin "31") (pinfunction "VCCIOB_31") (pintype "passive"))
      (node (ref "FT2232D") (pin "42") (pinfunction "VCC_42") (pintype "passive"))
      (node (ref "JP1") (pin "1") (pinfunction "1_1") (pintype "passive"))
      (node (ref "JP2") (pin "3") (pinfunction "3_3") (pintype "passive"))
      (node (ref "R19") (pin "2") (pinfunction "2_2") (pintype "passive"))
      (node (ref "R24") (pin "2") (pinfunction "2_2") (pintype "passive"))
      (node (ref "SPX1117") (pin "3") (pinfunction "Vin_3") (pintype "passive"))
      (node (ref "U3") (pin "1") (pinfunction "VCC_1") (pintype "passive"))
    )
    (net (code "107") (name "unconnected-(CAT93C46-NC-Pad7)") (class "Default")
      (node (ref "CAT93C46") (pin "7") (pinfunction "NC_7") (pintype "passive+no_connect"))
    )
    (net (code "108") (name "unconnected-(FT2232D-ACBBUS0-Pad15)") (class "Default")
      (node (ref "FT2232D") (pin "15") (pinfunction "ACBBUS0_15") (pintype "passive+no_connect"))
    )
    (net (code "109") (name "unconnected-(FT2232D-ACBBUS1-Pad13)") (class "Default")
      (node (ref "FT2232D") (pin "13") (pinfunction "ACBBUS1_13") (pintype "passive+no_connect"))
    )
    (net (code "110") (name "unconnected-(FT2232D-ACBBUS2-Pad12)") (class "Default")
      (node (ref "FT2232D") (pin "12") (pinfunction "ACBBUS2_12") (pintype "passive+no_connect"))
    )
    (net (code "111") (name "unconnected-(FT2232D-ACBBUS3-Pad11)") (class "Default")
      (node (ref "FT2232D") (pin "11") (pinfunction "ACBBUS3_11") (pintype "passive+no_connect"))
    )
    (net (code "112") (name "unconnected-(FT2232D-ADBUS4-Pad20)") (class "Default")
      (node (ref "FT2232D") (pin "20") (pinfunction "ADBUS4_20") (pintype "passive+no_connect"))
    )
    (net (code "113") (name "unconnected-(FT2232D-ADBUS6-Pad17)") (class "Default")
      (node (ref "FT2232D") (pin "17") (pinfunction "ADBUS6_17") (pintype "passive+no_connect"))
    )
    (net (code "114") (name "unconnected-(FT2232D-ADBUS7-Pad16)") (class "Default")
      (node (ref "FT2232D") (pin "16") (pinfunction "ADBUS7_16") (pintype "passive+no_connect"))
    )
    (net (code "115") (name "unconnected-(FT2232D-BCBUS0-Pad30)") (class "Default")
      (node (ref "FT2232D") (pin "30") (pinfunction "BCBUS0_30") (pintype "passive+no_connect"))
    )
    (net (code "116") (name "unconnected-(FT2232D-BCBUS1-Pad29)") (class "Default")
      (node (ref "FT2232D") (pin "29") (pinfunction "BCBUS1_29") (pintype "passive+no_connect"))
    )
    (net (code "117") (name "unconnected-(FT2232D-BCBUS2-Pad28)") (class "Default")
      (node (ref "FT2232D") (pin "28") (pinfunction "BCBUS2_28") (pintype "passive+no_connect"))
    )
    (net (code "118") (name "unconnected-(FT2232D-BCBUS3-Pad27)") (class "Default")
      (node (ref "FT2232D") (pin "27") (pinfunction "BCBUS3_27") (pintype "passive+no_connect"))
    )
    (net (code "119") (name "unconnected-(FT2232D-BDBUS2-Pad38)") (class "Default")
      (node (ref "FT2232D") (pin "38") (pinfunction "BDBUS2_38") (pintype "passive+no_connect"))
    )
    (net (code "120") (name "unconnected-(FT2232D-BDBUS3-Pad37)") (class "Default")
      (node (ref "FT2232D") (pin "37") (pinfunction "BDBUS3_37") (pintype "passive+no_connect"))
    )
    (net (code "121") (name "unconnected-(FT2232D-BDBUS4-Pad36)") (class "Default")
      (node (ref "FT2232D") (pin "36") (pinfunction "BDBUS4_36") (pintype "passive+no_connect"))
    )
    (net (code "122") (name "unconnected-(FT2232D-BDBUS5-Pad35)") (class "Default")
      (node (ref "FT2232D") (pin "35") (pinfunction "BDBUS5_35") (pintype "passive+no_connect"))
    )
    (net (code "123") (name "unconnected-(FT2232D-BDBUS6-Pad33)") (class "Default")
      (node (ref "FT2232D") (pin "33") (pinfunction "BDBUS6_33") (pintype "passive+no_connect"))
    )
    (net (code "124") (name "unconnected-(FT2232D-BDBUS7-Pad32)") (class "Default")
      (node (ref "FT2232D") (pin "32") (pinfunction "BDBUS7_32") (pintype "passive+no_connect"))
    )
    (net (code "125") (name "unconnected-(FT2232D-PWREN#-Pad41)") (class "Default")
      (node (ref "FT2232D") (pin "41") (pinfunction "PWREN#_41") (pintype "passive+no_connect"))
    )
    (net (code "126") (name "unconnected-(JTAG-NC-Pad17)") (class "Default")
      (node (ref "JTAG") (pin "17") (pinfunction "NC_17") (pintype "passive+no_connect"))
    )
    (net (code "127") (name "unconnected-(JTAG-NC-Pad19)") (class "Default")
      (node (ref "JTAG") (pin "19") (pinfunction "NC_19") (pintype "passive+no_connect"))
    )
    (net (code "128") (name "unconnected-(JTAG-RTCK-Pad11)") (class "Default")
      (node (ref "JTAG") (pin "11") (pinfunction "RTCK_11") (pintype "passive+no_connect"))
    )
    (net (code "129") (name "unconnected-(JTAG-~{SRST}-Pad15)") (class "Default")
      (node (ref "JTAG") (pin "15") (pinfunction "~{SRST}_15") (pintype "passive+no_connect"))
    )
    (net (code "130") (name "unconnected-(JTAG-~{TRST}-Pad3)") (class "Default")
      (node (ref "JTAG") (pin "3") (pinfunction "~{TRST}_3") (pintype "passive+no_connect"))
    )
    (net (code "131") (name "unconnected-(LM1138-NC-Pad36)") (class "Default")
      (node (ref "LM1138") (pin "36") (pinfunction "NC_36") (pintype "passive+no_connect"))
    )
    (net (code "132") (name "unconnected-(LM1138-NC-Pad37)") (class "Default")
      (node (ref "LM1138") (pin "37") (pinfunction "NC_37") (pintype "passive+no_connect"))
    )
    (net (code "133") (name "unconnected-(LM1138-NC-Pad83)") (class "Default")
      (node (ref "LM1138") (pin "83") (pinfunction "NC_83") (pintype "passive+no_connect"))
    )
    (net (code "134") (name "unconnected-(LM1138-NC-Pad84)") (class "Default")
      (node (ref "LM1138") (pin "84") (pinfunction "NC_84") (pintype "passive+no_connect"))
    )
    (net (code "135") (name "unconnected-(LM1138-NC-Pad85)") (class "Default")
      (node (ref "LM1138") (pin "85") (pinfunction "NC_85") (pintype "passive+no_connect"))
    )
    (net (code "136") (name "unconnected-(LM1138-NC-Pad86)") (class "Default")
      (node (ref "LM1138") (pin "86") (pinfunction "NC_86") (pintype "passive+no_connect"))
    )
    (net (code "137") (name "unconnected-(U3-NC-Pad5)") (class "Default")
      (node (ref "U3") (pin "5") (pinfunction "NC_5") (pintype "passive"))
    )
    (net (code "138") (name "unconnected-(U3-NC-Pad6)") (class "Default")
      (node (ref "U3") (pin "6") (pinfunction "NC_6") (pintype "passive"))
    )
  )
)
